# 01-POWER.net
KiCad netlist of a schematic drawn in Altium Designer
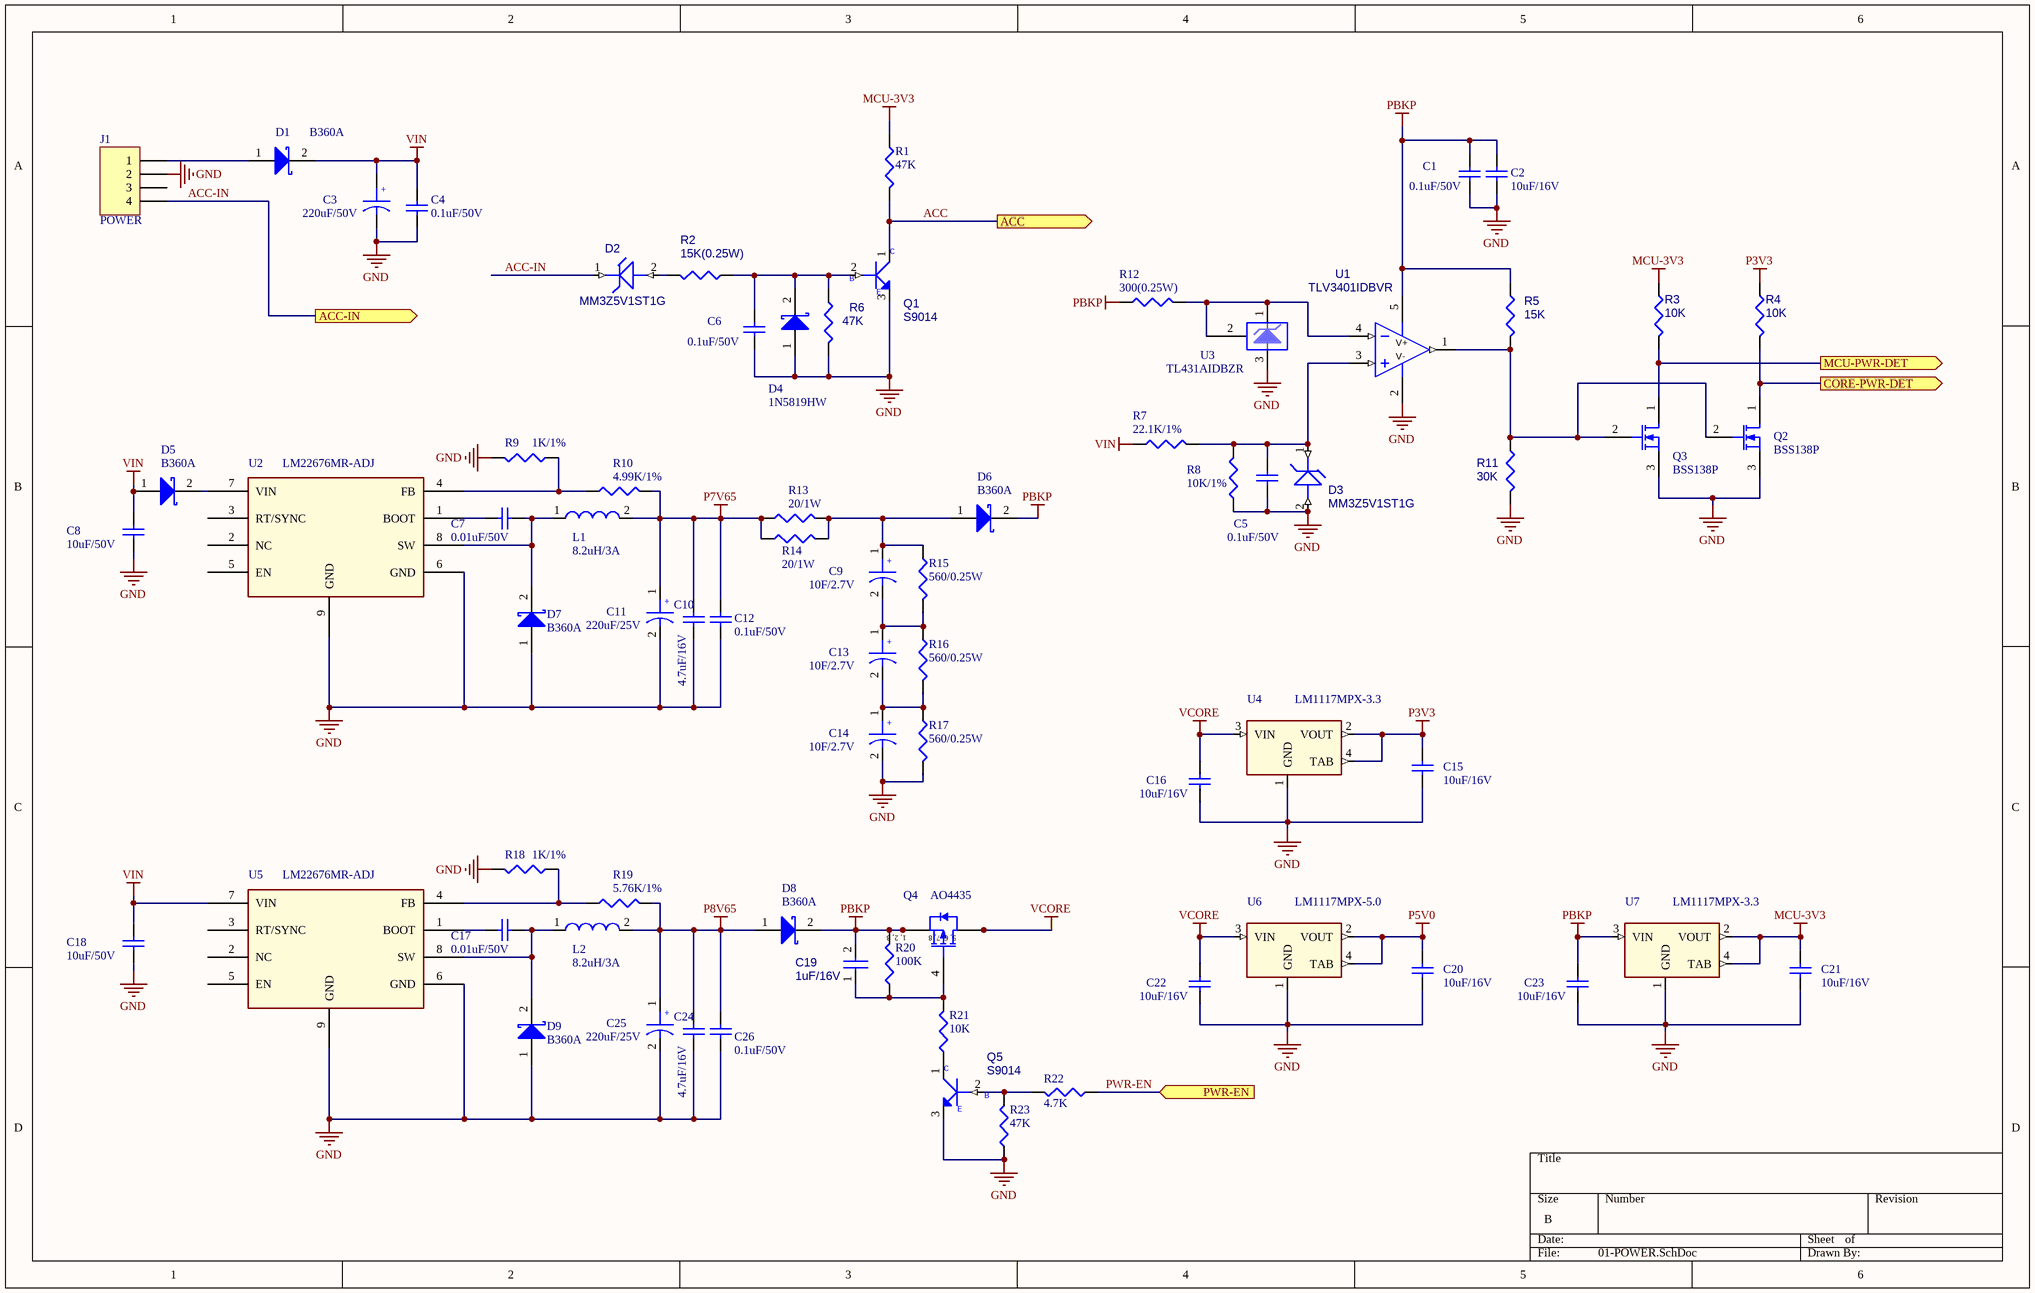
[diagram p0: 01-POWER.SchDoc]

(export (version "E")
  (design (tool "Eeschema 10.0.6"))
  (components
    (comp (ref "C1")
      (value "0.1uF/50V")
      (footprint "0402")
      (description "Capacitor")
      (fields (field (name "PUBLISHER") "Altium Limited"))
      (libsource (lib "Miscellaneous Devices") (part "Cap"))
    )
    (comp (ref "C2")
      (value "10uF/16V")
      (footprint "0805")
      (description "Capacitor")
      (fields (field (name "PUBLISHER") "Altium Limited"))
      (libsource (lib "Miscellaneous Devices") (part "Cap"))
    )
    (comp (ref "C3") (value "220uF/50V") (footprint "DL-10*10.5") (libsource (lib "") (part "CAP WP_1")))
    (comp (ref "C4")
      (value "0.1uF/50V")
      (footprint "0402")
      (description "Capacitor")
      (fields (field (name "PUBLISHER") "Altium Limited"))
      (libsource (lib "Miscellaneous Devices") (part "Cap"))
    )
    (comp (ref "C5")
      (value "0.1uF/50V")
      (footprint "0402")
      (description "Capacitor")
      (fields (field (name "PUBLISHER") "Altium Limited"))
      (libsource (lib "Miscellaneous Devices") (part "Cap"))
    )
    (comp (ref "C6")
      (value "0.1uF/50V")
      (footprint "0402")
      (description "Capacitor")
      (fields (field (name "PUBLISHER") "Altium Limited"))
      (libsource (lib "Miscellaneous Devices") (part "Cap"))
    )
    (comp (ref "C7")
      (value "0.01uF/50V")
      (footprint "0402")
      (description "Capacitor")
      (fields (field (name "PUBLISHER") "Altium Limited"))
      (libsource (lib "Miscellaneous Devices") (part "Cap"))
    )
    (comp (ref "C8")
      (value "10uF/50V")
      (footprint "1210")
      (description "Capacitor")
      (fields (field (name "PUBLISHER") "Altium Limited"))
      (libsource (lib "Miscellaneous Devices") (part "Cap"))
    )
    (comp (ref "C9") (value "10F/2.7V") (footprint "SUPERCAP") (libsource (lib "*") (part "CAP WP")))
    (comp (ref "C10")
      (value "4.7uF/16V")
      (footprint "0805")
      (description "Capacitor")
      (fields (field (name "PUBLISHER") "Altium Limited"))
      (libsource (lib "Miscellaneous Devices") (part "Cap"))
    )
    (comp (ref "C11") (value "220uF/25V") (footprint "DL-8*10.5") (libsource (lib "*") (part "CAP WP")))
    (comp (ref "C12")
      (value "0.1uF/50V")
      (footprint "0402")
      (description "Capacitor")
      (fields (field (name "PUBLISHER") "Altium Limited"))
      (libsource (lib "Miscellaneous Devices") (part "Cap"))
    )
    (comp (ref "C13") (value "10F/2.7V") (footprint "SUPERCAP") (libsource (lib "*") (part "CAP WP")))
    (comp (ref "C14") (value "10F/2.7V") (footprint "SUPERCAP") (libsource (lib "*") (part "CAP WP")))
    (comp (ref "C15")
      (value "10uF/16V")
      (footprint "0805")
      (description "Capacitor")
      (fields (field (name "PUBLISHER") "Altium Limited"))
      (libsource (lib "Miscellaneous Devices") (part "Cap"))
    )
    (comp (ref "C16")
      (value "10uF/16V")
      (footprint "0805")
      (description "Capacitor")
      (fields (field (name "PUBLISHER") "Altium Limited"))
      (libsource (lib "Miscellaneous Devices") (part "Cap"))
    )
    (comp (ref "C17")
      (value "0.01uF/50V")
      (footprint "0402")
      (description "Capacitor")
      (fields (field (name "PUBLISHER") "Altium Limited"))
      (libsource (lib "Miscellaneous Devices") (part "Cap"))
    )
    (comp (ref "C18")
      (value "10uF/50V")
      (footprint "1210")
      (description "Capacitor")
      (fields (field (name "PUBLISHER") "Altium Limited"))
      (libsource (lib "Miscellaneous Devices") (part "Cap"))
    )
    (comp (ref "C19") (value "1uF/16V") (footprint "0603") (libsource (lib "*") (part "CAP NP_Dup2")))
    (comp (ref "C20")
      (value "10uF/16V")
      (footprint "0805")
      (description "Capacitor")
      (fields (field (name "PUBLISHER") "Altium Limited"))
      (libsource (lib "Miscellaneous Devices") (part "Cap"))
    )
    (comp (ref "C21")
      (value "10uF/16V")
      (footprint "0805")
      (description "Capacitor")
      (fields (field (name "PUBLISHER") "Altium Limited"))
      (libsource (lib "Miscellaneous Devices") (part "Cap"))
    )
    (comp (ref "C22")
      (value "10uF/16V")
      (footprint "0805")
      (description "Capacitor")
      (fields (field (name "PUBLISHER") "Altium Limited"))
      (libsource (lib "Miscellaneous Devices") (part "Cap"))
    )
    (comp (ref "C23")
      (value "10uF/16V")
      (footprint "0805")
      (description "Capacitor")
      (fields (field (name "PUBLISHER") "Altium Limited"))
      (libsource (lib "Miscellaneous Devices") (part "Cap"))
    )
    (comp (ref "C24")
      (value "4.7uF/16V")
      (footprint "0805")
      (description "Capacitor")
      (fields (field (name "PUBLISHER") "Altium Limited"))
      (libsource (lib "Miscellaneous Devices") (part "Cap"))
    )
    (comp (ref "C25") (value "220uF/25V") (footprint "DL-8*10.5") (libsource (lib "*") (part "CAP WP")))
    (comp (ref "C26")
      (value "0.1uF/50V")
      (footprint "0402")
      (description "Capacitor")
      (fields (field (name "PUBLISHER") "Altium Limited"))
      (libsource (lib "Miscellaneous Devices") (part "Cap"))
    )
    (comp (ref "D1")
      (value "B360A")
      (footprint "B320A")
      (description "Schottky Rectifier")
      (libsource (lib "Miscellaneous Devices") (part "Diode 11DQ03"))
    )
    (comp (ref "D2")
      (value "MM3Z5V1ST1G")
      (footprint "SOD323F")
      (libsource (lib "*") (part "MMGZ5231BPTLL34"))
    )
    (comp (ref "D3")
      (value "MM3Z5V1ST1G")
      (footprint "SOD323F")
      (libsource (lib "*") (part "MMGZ5231BPTLL34"))
    )
    (comp (ref "D4")
      (value "1N5819HW")
      (footprint "1N5819")
      (description "Schottky Rectifier")
      (libsource (lib "Miscellaneous Devices") (part "Diode 11DQ03"))
    )
    (comp (ref "D5")
      (value "B360A")
      (footprint "B320A")
      (description "Schottky Rectifier")
      (libsource (lib "Miscellaneous Devices") (part "Diode 11DQ03"))
    )
    (comp (ref "D6")
      (value "B360A")
      (footprint "B320A")
      (description "Schottky Rectifier")
      (libsource (lib "Miscellaneous Devices") (part "Diode 11DQ03"))
    )
    (comp (ref "D7")
      (value "B360A")
      (footprint "B320A")
      (description "Schottky Rectifier")
      (libsource (lib "Miscellaneous Devices") (part "Diode 11DQ03"))
    )
    (comp (ref "D8")
      (value "B360A")
      (footprint "B320A")
      (description "Schottky Rectifier")
      (libsource (lib "Miscellaneous Devices") (part "Diode 11DQ03"))
    )
    (comp (ref "D9")
      (value "B360A")
      (footprint "B320A")
      (description "Schottky Rectifier")
      (libsource (lib "Miscellaneous Devices") (part "Diode 11DQ03"))
    )
    (comp (ref "J1")
      (value "POWER")
      (footprint "3030WV-F-2*2P")
      (description "Header, 4-Pin")
      (fields (field (name "PUBLISHER") "Altium Limited"))
      (libsource (lib "Miscellaneous Connectors") (part "Header 4"))
    )
    (comp (ref "L1")
      (value "8.2uH/3A")
      (footprint "IND_10X10")
      (fields (field (name "PART NUMBER") "SH00000AJ00"))
      (libsource (lib "*") (part "4.7UH_CDH2D09BNP-4R7MC_0.7A_20%"))
    )
    (comp (ref "L2")
      (value "8.2uH/3A")
      (footprint "IND_10X10")
      (fields (field (name "PART NUMBER") "SH00000AJ00"))
      (libsource (lib "*") (part "4.7UH_CDH2D09BNP-4R7MC_0.7A_20%"))
    )
    (comp (ref "Q1")
      (value "S9014")
      (footprint "NPN")
      (fields (field (name "PART NUMBER") "SB039040000"))
      (libsource (lib "*") (part "MMBT3904_NL_SOT23-3"))
    )
    (comp (ref "Q2")
      (value "BSS138P")
      (footprint "NPN")
      (description "N-Channel MOSFET")
      (fields (field (name "PUBLISHER") "Altium Limited"))
      (libsource (lib "Miscellaneous Devices") (part "MOSFET-N"))
    )
    (comp (ref "Q3")
      (value "BSS138P")
      (footprint "NPN")
      (description "N-Channel MOSFET")
      (fields (field (name "PUBLISHER") "Altium Limited"))
      (libsource (lib "Miscellaneous Devices") (part "MOSFET-N"))
    )
    (comp (ref "Q4")
      (value "AO4435")
      (footprint "SO8")
      (description "P-Channel 30V (D-S)  MOSFET")
      (fields (field (name "PUBLISHER") "Altium Limited"))
      (libsource (lib "Vishay Siliconix Discrete MOSFET") (part "SI4431DY"))
    )
    (comp (ref "Q5")
      (value "S9014")
      (footprint "NPN")
      (fields (field (name "PART NUMBER") "SB039040000"))
      (libsource (lib "*") (part "MMBT3904_NL_SOT23-3"))
    )
    (comp (ref "R1") (value "47K") (footprint "0402") (libsource (lib "*") (part "CR16-1003FM")))
    (comp (ref "R2") (value "15K(0.25W)") (libsource (lib "*") (part "R")))
    (comp (ref "R3") (value "10K") (libsource (lib "*") (part "R")))
    (comp (ref "R4") (value "10K") (libsource (lib "*") (part "R")))
    (comp (ref "R5") (value "15K") (libsource (lib "*") (part "R")))
    (comp (ref "R6") (value "47K") (libsource (lib "*") (part "R")))
    (comp (ref "R7") (value "22.1K/1%") (footprint "0402") (libsource (lib "*") (part "CR16-1003FM")))
    (comp (ref "R8") (value "10K/1%") (footprint "0402") (libsource (lib "*") (part "CR16-1003FM")))
    (comp (ref "R9")
      (value "1K/1%")
      (footprint "0402")
      (description "Resistor")
      (fields (field (name "PUBLISHER") "Altium Limited"))
      (libsource (lib "Miscellaneous Devices") (part "Res3"))
    )
    (comp (ref "R10")
      (value "4.99K/1%")
      (footprint "0402")
      (description "Resistor")
      (fields (field (name "PUBLISHER") "Altium Limited"))
      (libsource (lib "Miscellaneous Devices") (part "Res3"))
    )
    (comp (ref "R11") (value "30K") (libsource (lib "*") (part "R")))
    (comp (ref "R12") (value "300(0.25W)") (footprint "1206") (libsource (lib "*") (part "CR16-1003FM")))
    (comp (ref "R13")
      (value "20/1W")
      (footprint "2512")
      (description "Resistor")
      (fields (field (name "PUBLISHER") "Altium Limited"))
      (libsource (lib "Miscellaneous Devices") (part "Res3"))
    )
    (comp (ref "R14")
      (value "20/1W")
      (footprint "2512")
      (description "Resistor")
      (fields (field (name "PUBLISHER") "Altium Limited"))
      (libsource (lib "Miscellaneous Devices") (part "Res3"))
    )
    (comp (ref "R15")
      (value "560/0.25W")
      (footprint "1206")
      (description "Resistor")
      (fields (field (name "PUBLISHER") "Altium Limited"))
      (libsource (lib "Miscellaneous Devices") (part "Res3"))
    )
    (comp (ref "R16")
      (value "560/0.25W")
      (footprint "1206")
      (description "Resistor")
      (fields (field (name "PUBLISHER") "Altium Limited"))
      (libsource (lib "Miscellaneous Devices") (part "Res3"))
    )
    (comp (ref "R17")
      (value "560/0.25W")
      (footprint "1206")
      (description "Resistor")
      (fields (field (name "PUBLISHER") "Altium Limited"))
      (libsource (lib "Miscellaneous Devices") (part "Res3"))
    )
    (comp (ref "R18")
      (value "1K/1%")
      (footprint "0402")
      (description "Resistor")
      (fields (field (name "PUBLISHER") "Altium Limited"))
      (libsource (lib "Miscellaneous Devices") (part "Res3"))
    )
    (comp (ref "R19")
      (value "5.76K/1%")
      (footprint "0402")
      (description "Resistor")
      (fields (field (name "PUBLISHER") "Altium Limited"))
      (libsource (lib "Miscellaneous Devices") (part "Res3"))
    )
    (comp (ref "R20") (value "100K") (footprint "0402") (libsource (lib "*") (part "CR16-1003FM")))
    (comp (ref "R21") (value "10K") (footprint "0402") (libsource (lib "*") (part "CR16-1003FM")))
    (comp (ref "R22") (value "4.7K") (footprint "0402") (libsource (lib "*") (part "CR16-1003FM")))
    (comp (ref "R23") (value "47K") (footprint "0402") (libsource (lib "*") (part "CR16-1003FM")))
    (comp (ref "U1")
      (value "TLV3401IDBVR")
      (footprint "SOT23-5")
      (description "Single 30V High Output Current and Unlimited Capacitive Load Op Amp")
      (fields
        (field (name "PARTNUMBER") "LM7321MF")
        (field (name "MANUFACTURER") "National Semiconductor")
        (field (name "PUBLISHER") "National Semiconductor")
      )
      (libsource (lib "NSC Amplifier") (part "LM7321MF"))
    )
    (comp (ref "U2") (value "LM22676MR-ADJ") (libsource (lib "*") (part "LM22670_0")))
    (comp (ref "U3")
      (value "TL431AIDBZR")
      (footprint "SOT23-3")
      (libsource (lib "Schlib") (part "TL431AIDBZR"))
    )
    (comp (ref "U4")
      (value "LM1117MPX-3.3")
      (footprint "AMS1117")
      (description "IC VREG LDO 1.8V 1A 10V SOT-223")
      (libsource (lib "*") (part "LD1117AS18"))
    )
    (comp (ref "U5") (value "LM22676MR-ADJ") (libsource (lib "*") (part "LM22670_0")))
    (comp (ref "U6")
      (value "LM1117MPX-5.0")
      (footprint "AMS1117")
      (description "IC VREG LDO 1.8V 1A 10V SOT-223")
      (libsource (lib "*") (part "LD1117AS18"))
    )
    (comp (ref "U7")
      (value "LM1117MPX-3.3")
      (footprint "AMS1117")
      (description "IC VREG LDO 1.8V 1A 10V SOT-223")
      (libsource (lib "*") (part "LD1117AS18"))
    )
  )
  (nets
    (net (code "1") (name "/ACC") (class "Default")
      (node (ref "Q1") (pin "1") (pinfunction "COLLECTOR_1") (pintype "passive"))
      (node (ref "R1") (pin "2") (pinfunction "2_2") (pintype "passive"))
    )
    (net (code "2") (name "/ACC-IN") (class "Default")
      (node (ref "D2") (pin "1") (pinfunction "1_1") (pintype "input"))
      (node (ref "J1") (pin "4") (pinfunction "4_4") (pintype "passive"))
    )
    (net (code "3") (name "/CORE-PWR-DET") (class "Default")
      (node (ref "Q2") (pin "1") (pinfunction "D_1") (pintype "passive"))
      (node (ref "R4") (pin "2") (pinfunction "2_2") (pintype "passive"))
    )
    (net (code "4") (name "/MCU-PWR-DET") (class "Default")
      (node (ref "Q3") (pin "1") (pinfunction "D_1") (pintype "passive"))
      (node (ref "R3") (pin "2") (pinfunction "2_2") (pintype "passive"))
    )
    (net (code "5") (name "/PWR-EN") (class "Default")
      (node (ref "R22") (pin "1") (pinfunction "1_1") (pintype "passive"))
    )
    (net (code "6") (name "GND") (class "Default")
      (node (ref "C1") (pin "2") (pinfunction "2_2") (pintype "passive"))
      (node (ref "C10") (pin "1") (pinfunction "1_1") (pintype "passive"))
      (node (ref "C11") (pin "2") (pinfunction "2_2") (pintype "passive"))
      (node (ref "C12") (pin "1") (pinfunction "1_1") (pintype "passive"))
      (node (ref "C14") (pin "2") (pinfunction "2_2") (pintype "passive"))
      (node (ref "C15") (pin "2") (pinfunction "2_2") (pintype "passive"))
      (node (ref "C16") (pin "2") (pinfunction "2_2") (pintype "passive"))
      (node (ref "C18") (pin "2") (pinfunction "2_2") (pintype "passive"))
      (node (ref "C2") (pin "1") (pinfunction "1_1") (pintype "passive"))
      (node (ref "C20") (pin "2") (pinfunction "2_2") (pintype "passive"))
      (node (ref "C21") (pin "2") (pinfunction "2_2") (pintype "passive"))
      (node (ref "C22") (pin "2") (pinfunction "2_2") (pintype "passive"))
      (node (ref "C23") (pin "2") (pinfunction "2_2") (pintype "passive"))
      (node (ref "C24") (pin "1") (pinfunction "1_1") (pintype "passive"))
      (node (ref "C25") (pin "2") (pinfunction "2_2") (pintype "passive"))
      (node (ref "C26") (pin "1") (pinfunction "1_1") (pintype "passive"))
      (node (ref "C3") (pin "2") (pinfunction "2_2") (pintype "passive"))
      (node (ref "C4") (pin "1") (pinfunction "1_1") (pintype "passive"))
      (node (ref "C5") (pin "1") (pinfunction "1_1") (pintype "passive"))
      (node (ref "C6") (pin "2") (pinfunction "2_2") (pintype "passive"))
      (node (ref "C8") (pin "2") (pinfunction "2_2") (pintype "passive"))
      (node (ref "D3") (pin "2") (pinfunction "2_2") (pintype "input"))
      (node (ref "D4") (pin "1") (pinfunction "A_1") (pintype "passive"))
      (node (ref "D7") (pin "1") (pinfunction "A_1") (pintype "passive"))
      (node (ref "D9") (pin "1") (pinfunction "A_1") (pintype "passive"))
      (node (ref "J1") (pin "2") (pinfunction "2_2") (pintype "passive"))
      (node (ref "Q1") (pin "3") (pinfunction "EMITTER_3") (pintype "passive"))
      (node (ref "Q2") (pin "3") (pinfunction "S_3") (pintype "passive"))
      (node (ref "Q3") (pin "3") (pinfunction "S_3") (pintype "passive"))
      (node (ref "Q5") (pin "3") (pinfunction "EMITTER_3") (pintype "passive"))
      (node (ref "R11") (pin "2") (pinfunction "2_2") (pintype "passive"))
      (node (ref "R17") (pin "2") (pinfunction "2_2") (pintype "passive"))
      (node (ref "R18") (pin "2") (pinfunction "2_2") (pintype "passive"))
      (node (ref "R23") (pin "1") (pinfunction "1_1") (pintype "passive"))
      (node (ref "R6") (pin "2") (pinfunction "2_2") (pintype "passive"))
      (node (ref "R8") (pin "1") (pinfunction "1_1") (pintype "passive"))
      (node (ref "R9") (pin "2") (pinfunction "2_2") (pintype "passive"))
      (node (ref "U1") (pin "2") (pinfunction "V-_2") (pintype "power_in"))
      (node (ref "U2") (pin "6") (pinfunction "GND_6") (pintype "passive"))
      (node (ref "U2") (pin "9") (pinfunction "GND_9") (pintype "power_in"))
      (node (ref "U3") (pin "3") (pinfunction "A_3") (pintype "passive"))
      (node (ref "U4") (pin "1") (pinfunction "GND_1") (pintype "power_in"))
      (node (ref "U5") (pin "6") (pinfunction "GND_6") (pintype "passive"))
      (node (ref "U5") (pin "9") (pinfunction "GND_9") (pintype "power_in"))
      (node (ref "U6") (pin "1") (pinfunction "GND_1") (pintype "power_in"))
      (node (ref "U7") (pin "1") (pinfunction "GND_1") (pintype "power_in"))
    )
    (net (code "7") (name "MCU-3V3") (class "Default")
      (node (ref "C21") (pin "1") (pinfunction "1_1") (pintype "passive"))
      (node (ref "R1") (pin "1") (pinfunction "1_1") (pintype "passive"))
      (node (ref "R3") (pin "1") (pinfunction "1_1") (pintype "passive"))
      (node (ref "U7") (pin "2") (pinfunction "VOUT_2") (pintype "output"))
      (node (ref "U7") (pin "4") (pinfunction "TAB_4") (pintype "output"))
    )
    (net (code "8") (name "Net-(C13-Pad1)") (class "Default")
      (node (ref "C13") (pin "1") (pinfunction "1_1") (pintype "passive"))
      (node (ref "C9") (pin "2") (pinfunction "2_2") (pintype "passive"))
      (node (ref "R15") (pin "2") (pinfunction "2_2") (pintype "passive"))
      (node (ref "R16") (pin "1") (pinfunction "1_1") (pintype "passive"))
    )
    (net (code "9") (name "Net-(C13-Pad2)") (class "Default")
      (node (ref "C13") (pin "2") (pinfunction "2_2") (pintype "passive"))
      (node (ref "C14") (pin "1") (pinfunction "1_1") (pintype "passive"))
      (node (ref "R16") (pin "2") (pinfunction "2_2") (pintype "passive"))
      (node (ref "R17") (pin "1") (pinfunction "1_1") (pintype "passive"))
    )
    (net (code "10") (name "Net-(D1-A)") (class "Default")
      (node (ref "D1") (pin "1") (pinfunction "A_1") (pintype "passive"))
      (node (ref "J1") (pin "1") (pinfunction "1_1") (pintype "passive"))
    )
    (net (code "11") (name "Net-(D2-Pad2)") (class "Default")
      (node (ref "D2") (pin "2") (pinfunction "2_2") (pintype "input"))
      (node (ref "R2") (pin "2") (pinfunction "2_2") (pintype "passive"))
    )
    (net (code "12") (name "Net-(D4-K)") (class "Default")
      (node (ref "C6") (pin "1") (pinfunction "1_1") (pintype "passive"))
      (node (ref "D4") (pin "2") (pinfunction "K_2") (pintype "passive"))
      (node (ref "Q1") (pin "2") (pinfunction "BASE_2") (pintype "input"))
      (node (ref "R2") (pin "1") (pinfunction "1_1") (pintype "passive"))
      (node (ref "R6") (pin "1") (pinfunction "1_1") (pintype "passive"))
    )
    (net (code "13") (name "Net-(D5-K)") (class "Default")
      (node (ref "D5") (pin "2") (pinfunction "K_2") (pintype "passive"))
      (node (ref "U2") (pin "7") (pinfunction "VIN_7") (pintype "power_in"))
    )
    (net (code "14") (name "Net-(D6-A)") (class "Default")
      (node (ref "C9") (pin "1") (pinfunction "1_1") (pintype "passive"))
      (node (ref "D6") (pin "1") (pinfunction "A_1") (pintype "passive"))
      (node (ref "R13") (pin "2") (pinfunction "2_2") (pintype "passive"))
      (node (ref "R14") (pin "2") (pinfunction "2_2") (pintype "passive"))
      (node (ref "R15") (pin "1") (pinfunction "1_1") (pintype "passive"))
    )
    (net (code "15") (name "Net-(D7-K)") (class "Default")
      (node (ref "C7") (pin "1") (pinfunction "1_1") (pintype "passive"))
      (node (ref "D7") (pin "2") (pinfunction "K_2") (pintype "passive"))
      (node (ref "L1") (pin "1") (pinfunction "1_1") (pintype "passive"))
      (node (ref "U2") (pin "8") (pinfunction "SW_8") (pintype "passive"))
    )
    (net (code "16") (name "Net-(D9-K)") (class "Default")
      (node (ref "C17") (pin "1") (pinfunction "1_1") (pintype "passive"))
      (node (ref "D9") (pin "2") (pinfunction "K_2") (pintype "passive"))
      (node (ref "L2") (pin "1") (pinfunction "1_1") (pintype "passive"))
      (node (ref "U5") (pin "8") (pinfunction "SW_8") (pintype "passive"))
    )
    (net (code "17") (name "Net-(Q2-G)") (class "Default")
      (node (ref "Q2") (pin "2") (pinfunction "G_2") (pintype "passive"))
      (node (ref "Q3") (pin "2") (pinfunction "G_2") (pintype "passive"))
      (node (ref "R11") (pin "1") (pinfunction "1_1") (pintype "passive"))
      (node (ref "R5") (pin "2") (pinfunction "2_2") (pintype "passive"))
      (node (ref "U1") (pin "1") (pinfunction "OUT_1") (pintype "output"))
    )
    (net (code "18") (name "Net-(Q4-G)") (class "Default")
      (node (ref "C19") (pin "1") (pinfunction "1_1") (pintype "passive"))
      (node (ref "Q4") (pin "4") (pinfunction "G_4") (pintype "passive"))
      (node (ref "R20") (pin "1") (pinfunction "1_1") (pintype "passive"))
      (node (ref "R21") (pin "2") (pinfunction "2_2") (pintype "passive"))
    )
    (net (code "19") (name "Net-(Q5-BASE)") (class "Default")
      (node (ref "Q5") (pin "2") (pinfunction "BASE_2") (pintype "input"))
      (node (ref "R22") (pin "2") (pinfunction "2_2") (pintype "passive"))
      (node (ref "R23") (pin "2") (pinfunction "2_2") (pintype "passive"))
    )
    (net (code "20") (name "Net-(Q5-COLLECTOR)") (class "Default")
      (node (ref "Q5") (pin "1") (pinfunction "COLLECTOR_1") (pintype "passive"))
      (node (ref "R21") (pin "1") (pinfunction "1_1") (pintype "passive"))
    )
    (net (code "21") (name "Net-(U1-IN+)") (class "Default")
      (node (ref "C5") (pin "2") (pinfunction "2_2") (pintype "passive"))
      (node (ref "D3") (pin "1") (pinfunction "1_1") (pintype "input"))
      (node (ref "R7") (pin "2") (pinfunction "2_2") (pintype "passive"))
      (node (ref "R8") (pin "2") (pinfunction "2_2") (pintype "passive"))
      (node (ref "U1") (pin "3") (pinfunction "IN+_3") (pintype "input"))
    )
    (net (code "22") (name "Net-(U1-IN-)") (class "Default")
      (node (ref "R12") (pin "2") (pinfunction "2_2") (pintype "passive"))
      (node (ref "U1") (pin "4") (pinfunction "IN-_4") (pintype "input"))
      (node (ref "U3") (pin "1") (pinfunction "K_1") (pintype "passive"))
      (node (ref "U3") (pin "2") (pinfunction "REF_2") (pintype "passive"))
    )
    (net (code "23") (name "Net-(U2-BOOT)") (class "Default")
      (node (ref "C7") (pin "2") (pinfunction "2_2") (pintype "passive"))
      (node (ref "U2") (pin "1") (pinfunction "BOOT_1") (pintype "passive"))
    )
    (net (code "24") (name "Net-(U2-FB)") (class "Default")
      (node (ref "R10") (pin "1") (pinfunction "1_1") (pintype "passive"))
      (node (ref "R9") (pin "1") (pinfunction "1_1") (pintype "passive"))
      (node (ref "U2") (pin "4") (pinfunction "FB_4") (pintype "passive"))
    )
    (net (code "25") (name "Net-(U5-BOOT)") (class "Default")
      (node (ref "C17") (pin "2") (pinfunction "2_2") (pintype "passive"))
      (node (ref "U5") (pin "1") (pinfunction "BOOT_1") (pintype "passive"))
    )
    (net (code "26") (name "Net-(U5-FB)") (class "Default")
      (node (ref "R18") (pin "1") (pinfunction "1_1") (pintype "passive"))
      (node (ref "R19") (pin "1") (pinfunction "1_1") (pintype "passive"))
      (node (ref "U5") (pin "4") (pinfunction "FB_4") (pintype "passive"))
    )
    (net (code "27") (name "P3V3") (class "Default")
      (node (ref "C15") (pin "1") (pinfunction "1_1") (pintype "passive"))
      (node (ref "R4") (pin "1") (pinfunction "1_1") (pintype "passive"))
      (node (ref "U4") (pin "2") (pinfunction "VOUT_2") (pintype "output"))
      (node (ref "U4") (pin "4") (pinfunction "TAB_4") (pintype "output"))
    )
    (net (code "28") (name "P5V0") (class "Default")
      (node (ref "C20") (pin "1") (pinfunction "1_1") (pintype "passive"))
      (node (ref "U6") (pin "2") (pinfunction "VOUT_2") (pintype "output"))
      (node (ref "U6") (pin "4") (pinfunction "TAB_4") (pintype "output"))
    )
    (net (code "29") (name "P7V65") (class "Default")
      (node (ref "C10") (pin "2") (pinfunction "2_2") (pintype "passive"))
      (node (ref "C11") (pin "1") (pinfunction "1_1") (pintype "passive"))
      (node (ref "C12") (pin "2") (pinfunction "2_2") (pintype "passive"))
      (node (ref "L1") (pin "2") (pinfunction "2_2") (pintype "passive"))
      (node (ref "R10") (pin "2") (pinfunction "2_2") (pintype "passive"))
      (node (ref "R13") (pin "1") (pinfunction "1_1") (pintype "passive"))
      (node (ref "R14") (pin "1") (pinfunction "1_1") (pintype "passive"))
    )
    (net (code "30") (name "P8V65") (class "Default")
      (node (ref "C24") (pin "2") (pinfunction "2_2") (pintype "passive"))
      (node (ref "C25") (pin "1") (pinfunction "1_1") (pintype "passive"))
      (node (ref "C26") (pin "2") (pinfunction "2_2") (pintype "passive"))
      (node (ref "D8") (pin "1") (pinfunction "A_1") (pintype "passive"))
      (node (ref "L2") (pin "2") (pinfunction "2_2") (pintype "passive"))
      (node (ref "R19") (pin "2") (pinfunction "2_2") (pintype "passive"))
    )
    (net (code "31") (name "PBKP") (class "Default")
      (node (ref "C1") (pin "1") (pinfunction "1_1") (pintype "passive"))
      (node (ref "C19") (pin "2") (pinfunction "2_2") (pintype "passive"))
      (node (ref "C2") (pin "2") (pinfunction "2_2") (pintype "passive"))
      (node (ref "C23") (pin "1") (pinfunction "1_1") (pintype "passive"))
      (node (ref "D6") (pin "2") (pinfunction "K_2") (pintype "passive"))
      (node (ref "D8") (pin "2") (pinfunction "K_2") (pintype "passive"))
      (node (ref "Q4") (pin "1") (pinfunction "S_1") (pintype "passive"))
      (node (ref "Q4") (pin "2") (pinfunction "S_2") (pintype "passive"))
      (node (ref "Q4") (pin "3") (pinfunction "S_3") (pintype "passive"))
      (node (ref "R12") (pin "1") (pinfunction "1_1") (pintype "passive"))
      (node (ref "R20") (pin "2") (pinfunction "2_2") (pintype "passive"))
      (node (ref "R5") (pin "1") (pinfunction "1_1") (pintype "passive"))
      (node (ref "U1") (pin "5") (pinfunction "V+_5") (pintype "power_in"))
      (node (ref "U7") (pin "3") (pinfunction "VIN_3") (pintype "input"))
    )
    (net (code "32") (name "VCORE") (class "Default")
      (node (ref "C16") (pin "1") (pinfunction "1_1") (pintype "passive"))
      (node (ref "C22") (pin "1") (pinfunction "1_1") (pintype "passive"))
      (node (ref "Q4") (pin "5") (pinfunction "D_5") (pintype "passive"))
      (node (ref "Q4") (pin "6") (pinfunction "D_6") (pintype "passive"))
      (node (ref "Q4") (pin "7") (pinfunction "D_7") (pintype "passive"))
      (node (ref "Q4") (pin "8") (pinfunction "D_8") (pintype "passive"))
      (node (ref "U4") (pin "3") (pinfunction "VIN_3") (pintype "input"))
      (node (ref "U6") (pin "3") (pinfunction "VIN_3") (pintype "input"))
    )
    (net (code "33") (name "VIN") (class "Default")
      (node (ref "C18") (pin "1") (pinfunction "1_1") (pintype "passive"))
      (node (ref "C3") (pin "1") (pinfunction "1_1") (pintype "passive"))
      (node (ref "C4") (pin "2") (pinfunction "2_2") (pintype "passive"))
      (node (ref "C8") (pin "1") (pinfunction "1_1") (pintype "passive"))
      (node (ref "D1") (pin "2") (pinfunction "K_2") (pintype "passive"))
      (node (ref "D5") (pin "1") (pinfunction "A_1") (pintype "passive"))
      (node (ref "R7") (pin "1") (pinfunction "1_1") (pintype "passive"))
      (node (ref "U5") (pin "7") (pinfunction "VIN_7") (pintype "power_in"))
    )
    (net (code "34") (name "unconnected-(J1-Pad3)") (class "Default")
      (node (ref "J1") (pin "3") (pinfunction "3_3") (pintype "passive"))
    )
    (net (code "35") (name "unconnected-(U2-EN-Pad5)") (class "Default")
      (node (ref "U2") (pin "5") (pinfunction "EN_5") (pintype "passive"))
    )
    (net (code "36") (name "unconnected-(U2-NC-Pad2)") (class "Default")
      (node (ref "U2") (pin "2") (pinfunction "NC_2") (pintype "passive"))
    )
    (net (code "37") (name "unconnected-(U2-RT{slash}SYNC-Pad3)") (class "Default")
      (node (ref "U2") (pin "3") (pinfunction "RT/SYNC_3") (pintype "passive"))
    )
    (net (code "38") (name "unconnected-(U5-EN-Pad5)") (class "Default")
      (node (ref "U5") (pin "5") (pinfunction "EN_5") (pintype "passive"))
    )
    (net (code "39") (name "unconnected-(U5-NC-Pad2)") (class "Default")
      (node (ref "U5") (pin "2") (pinfunction "NC_2") (pintype "passive"))
    )
    (net (code "40") (name "unconnected-(U5-RT{slash}SYNC-Pad3)") (class "Default")
      (node (ref "U5") (pin "3") (pinfunction "RT/SYNC_3") (pintype "passive"))
    )
  )
)
